# attiny_cool.net
KiCad netlist of a schematic drawn in EAGLE
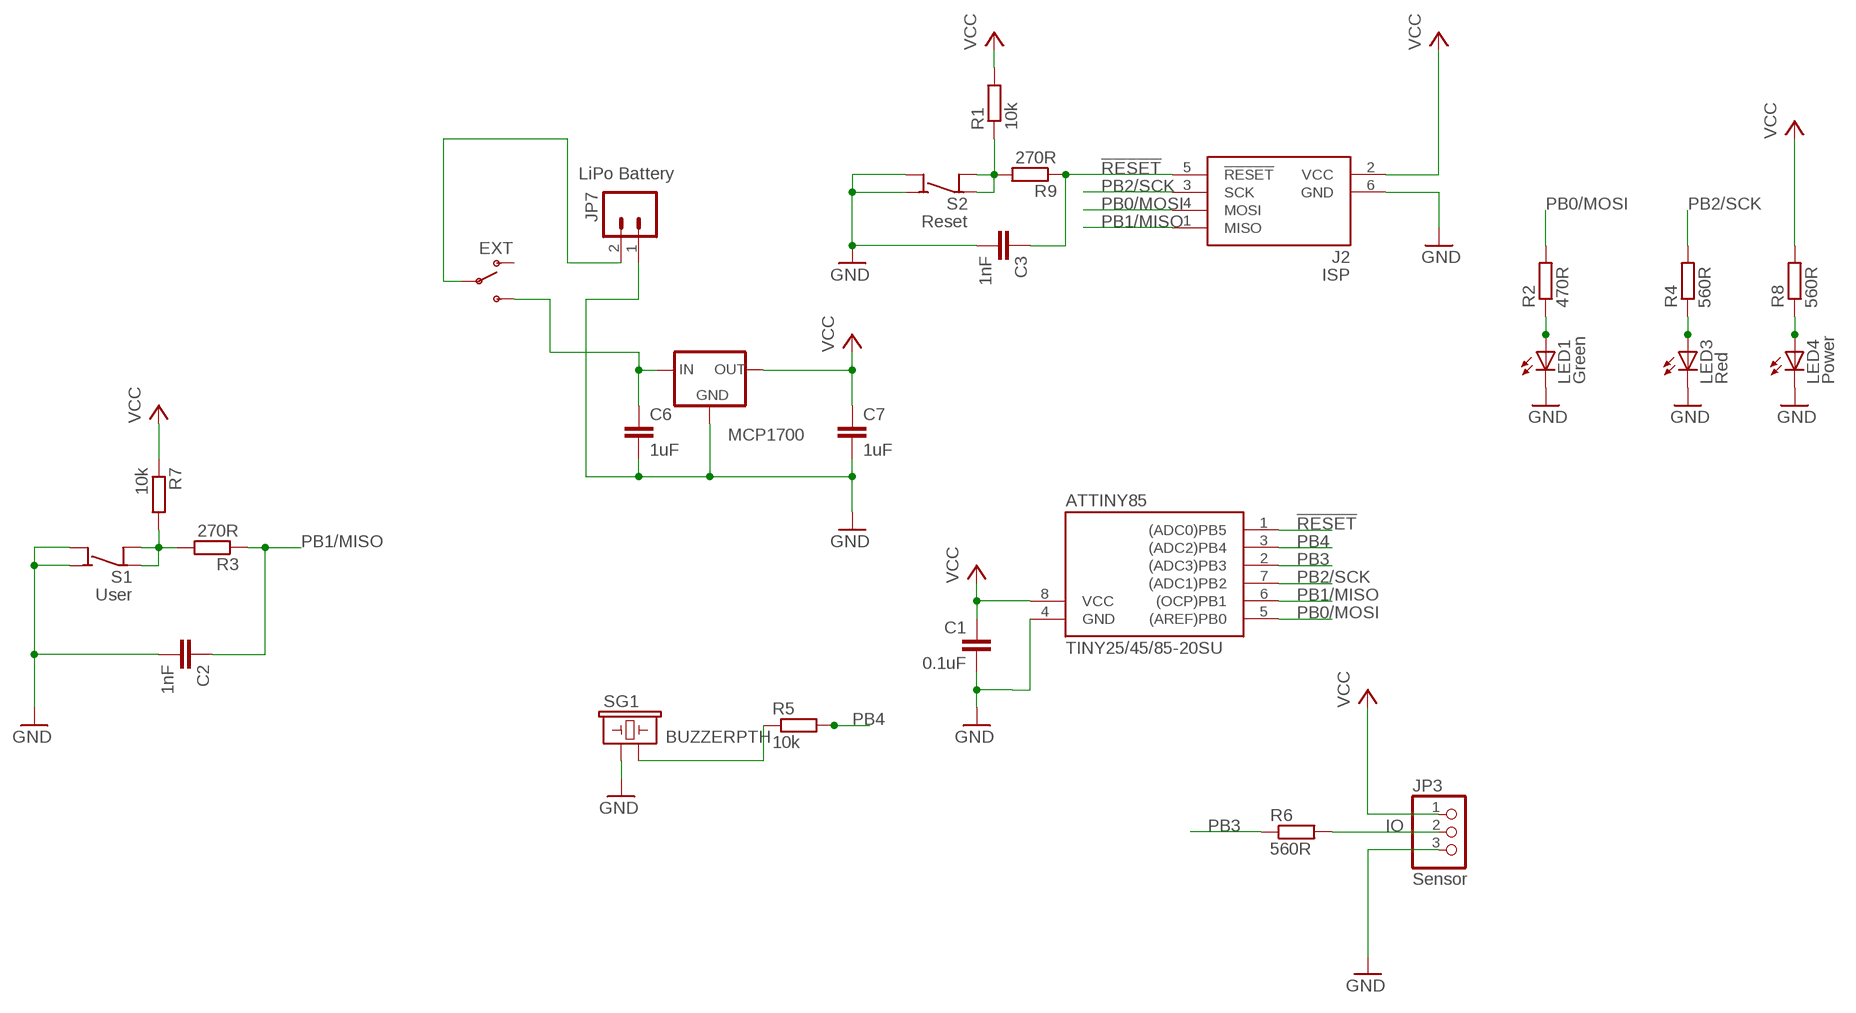
[diagram p0: schematic, sheet 1]

(export (version "E")
  (design (tool "Eeschema 10.0.6"))
  (components
    (comp (ref "ATTINY85")
      (value "TINY25/45/85-20SU")
      (footprint "eagle-import:SOIC8")
      (libsource (lib "eagle-import") (part "TINY25/45/85-20SU"))
    )
    (comp (ref "C1")
      (value "0.1uF")
      (footprint "eagle-import:C0805")
      (libsource (lib "eagle-import") (part "C-EUC0805"))
    )
    (comp (ref "C2")
      (value "1nF")
      (footprint "eagle-import:C0805")
      (libsource (lib "eagle-import") (part "C-EUC0805"))
    )
    (comp (ref "C3")
      (value "1nF")
      (footprint "eagle-import:C0805")
      (libsource (lib "eagle-import") (part "C-EUC0805"))
    )
    (comp (ref "C6")
      (value "1uF")
      (footprint "eagle-import:C0805")
      (libsource (lib "eagle-import") (part "C-EUC0805"))
    )
    (comp (ref "C7")
      (value "1uF")
      (footprint "eagle-import:C0805")
      (libsource (lib "eagle-import") (part "C-EUC0805"))
    )
    (comp (ref "J2")
      (value "ISP")
      (footprint "eagle-import:CON6P2R")
      (libsource (lib "eagle-import") (part "AVRISP6"))
    )
    (comp (ref "JP3")
      (value "Sensor")
      (footprint "eagle-import:1X03")
      (libsource (lib "eagle-import") (part "PINHD-1X3"))
    )
    (comp (ref "JP7")
      (value "LiPo Battery")
      (footprint "eagle-import:JST-2-PTH")
      (libsource (lib "eagle-import") (part "M02JST-PTH-2"))
    )
    (comp (ref "LED1")
      (value "Green")
      (footprint "eagle-import:CHIPLED_1206")
      (libsource (lib "eagle-import") (part "LEDCHIPLED_1206"))
    )
    (comp (ref "LED3")
      (value "Red")
      (footprint "eagle-import:CHIPLED_1206")
      (libsource (lib "eagle-import") (part "LEDCHIPLED_1206"))
    )
    (comp (ref "LED4")
      (value "Power")
      (footprint "eagle-import:CHIPLED_1206")
      (libsource (lib "eagle-import") (part "LEDCHIPLED_1206"))
    )
    (comp (ref "MCP1700")
      (value "MCP1700")
      (footprint "eagle-import:SOT-23")
      (libsource (lib "eagle-import") (part "MCP1700SOT-23"))
    )
    (comp (ref "ON")
      (value "EXT")
      (footprint "eagle-import:SWITCH-SPDT")
      (libsource (lib "eagle-import") (part "SWITCH-SPSTPTH"))
    )
    (comp (ref "R1")
      (value "10k")
      (footprint "eagle-import:R0805")
      (libsource (lib "eagle-import") (part "R-EU_R0805"))
    )
    (comp (ref "R2")
      (value "470R")
      (footprint "eagle-import:R0805")
      (libsource (lib "eagle-import") (part "R-EU_R0805"))
    )
    (comp (ref "R3")
      (value "270R")
      (footprint "eagle-import:R0805")
      (libsource (lib "eagle-import") (part "R-EU_R0805"))
    )
    (comp (ref "R4")
      (value "560R")
      (footprint "eagle-import:R0805")
      (libsource (lib "eagle-import") (part "R-EU_R0805"))
    )
    (comp (ref "R5")
      (value "10k")
      (footprint "eagle-import:R0805")
      (libsource (lib "eagle-import") (part "R-EU_R0805"))
    )
    (comp (ref "R6")
      (value "560R")
      (footprint "eagle-import:R0805")
      (libsource (lib "eagle-import") (part "R-EU_R0805"))
    )
    (comp (ref "R7")
      (value "10k")
      (footprint "eagle-import:R0805")
      (libsource (lib "eagle-import") (part "R-EU_R0805"))
    )
    (comp (ref "R8")
      (value "560R")
      (footprint "eagle-import:R0805")
      (libsource (lib "eagle-import") (part "R-EU_R0805"))
    )
    (comp (ref "R9")
      (value "270R")
      (footprint "eagle-import:R0805")
      (libsource (lib "eagle-import") (part "R-EU_R0805"))
    )
    (comp (ref "S1")
      (value "User")
      (footprint "eagle-import:6MMTACTILE_4PIN")
      (libsource (lib "eagle-import") (part "SPST4"))
    )
    (comp (ref "S2")
      (value "Reset")
      (footprint "eagle-import:6MMTACTILE_4PIN")
      (libsource (lib "eagle-import") (part "SPST4"))
    )
    (comp (ref "SG1")
      (value "BUZZERPTH")
      (footprint "eagle-import:BUZZER-12MM")
      (libsource (lib "eagle-import") (part "BUZZERPTH"))
    )
  )
  (nets
    (net (code "1") (name "/IO") (class "Default")
      (node (ref "JP3") (pin "2") (pinfunction "2_2") (pintype "passive"))
      (node (ref "R6") (pin "2") (pinfunction "2_2") (pintype "passive"))
    )
    (net (code "2") (name "/PB0{slash}MOSI") (class "Default")
      (node (ref "ATTINY85") (pin "5") (pinfunction "(AREF)PB0_5") (pintype "bidirectional"))
      (node (ref "J2") (pin "4") (pinfunction "MOSI_4") (pintype "output"))
      (node (ref "R2") (pin "2") (pinfunction "2_2") (pintype "passive"))
    )
    (net (code "3") (name "/PB1{slash}MISO") (class "Default")
      (node (ref "ATTINY85") (pin "6") (pinfunction "(OCP)PB1_6") (pintype "bidirectional"))
      (node (ref "C2") (pin "1") (pinfunction "1_1") (pintype "passive"))
      (node (ref "J2") (pin "1") (pinfunction "MISO_1") (pintype "input"))
      (node (ref "R3") (pin "1") (pinfunction "1_1") (pintype "passive"))
    )
    (net (code "4") (name "/PB2{slash}SCK") (class "Default")
      (node (ref "ATTINY85") (pin "7") (pinfunction "(ADC1)PB2_7") (pintype "bidirectional"))
      (node (ref "J2") (pin "3") (pinfunction "SCK_3") (pintype "output"))
      (node (ref "R4") (pin "2") (pinfunction "2_2") (pintype "passive"))
    )
    (net (code "5") (name "/PB3") (class "Default")
      (node (ref "ATTINY85") (pin "2") (pinfunction "(ADC3)PB3_2") (pintype "bidirectional"))
      (node (ref "R6") (pin "1") (pinfunction "1_1") (pintype "passive"))
    )
    (net (code "6") (name "/PB4") (class "Default")
      (node (ref "ATTINY85") (pin "3") (pinfunction "(ADC2)PB4_3") (pintype "bidirectional"))
      (node (ref "R5") (pin "2") (pinfunction "2_2") (pintype "passive"))
    )
    (net (code "7") (name "/~{RESET}") (class "Default")
      (node (ref "ATTINY85") (pin "1") (pinfunction "(ADC0)PB5_1") (pintype "bidirectional"))
      (node (ref "C3") (pin "1") (pinfunction "1_1") (pintype "passive"))
      (node (ref "J2") (pin "5") (pinfunction "~{RESET}_5") (pintype "output"))
      (node (ref "R9") (pin "1") (pinfunction "1_1") (pintype "passive"))
    )
    (net (code "8") (name "GND") (class "Default")
      (node (ref "ATTINY85") (pin "4") (pinfunction "GND_4") (pintype "power_in"))
      (node (ref "C1") (pin "2") (pinfunction "2_2") (pintype "passive"))
      (node (ref "C2") (pin "2") (pinfunction "2_2") (pintype "passive"))
      (node (ref "C3") (pin "2") (pinfunction "2_2") (pintype "passive"))
      (node (ref "C6") (pin "2") (pinfunction "2_2") (pintype "passive"))
      (node (ref "C7") (pin "2") (pinfunction "2_2") (pintype "passive"))
      (node (ref "J2") (pin "6") (pinfunction "GND_6") (pintype "power_in"))
      (node (ref "JP3") (pin "3") (pinfunction "3_3") (pintype "passive"))
      (node (ref "JP7") (pin "1") (pinfunction "1_1") (pintype "passive"))
      (node (ref "LED1") (pin "C") (pinfunction "C_C") (pintype "passive"))
      (node (ref "LED3") (pin "C") (pinfunction "C_C") (pintype "passive"))
      (node (ref "LED4") (pin "C") (pinfunction "C_C") (pintype "passive"))
      (node (ref "MCP1700") (pin "1") (pinfunction "GND_1") (pintype "input"))
      (node (ref "S1") (pin "A1") (pinfunction "NO_A1") (pintype "passive"))
      (node (ref "S1") (pin "A2") (pinfunction "NO_A2") (pintype "passive"))
      (node (ref "S2") (pin "A1") (pinfunction "NO_A1") (pintype "passive"))
      (node (ref "S2") (pin "A2") (pinfunction "NO_A2") (pintype "passive"))
      (node (ref "SG1") (pin "+") (pinfunction "1_+") (pintype "passive"))
    )
    (net (code "9") (name "Net-(LED1-PadA)") (class "Default")
      (node (ref "LED1") (pin "A") (pinfunction "A_A") (pintype "passive"))
      (node (ref "R2") (pin "1") (pinfunction "1_1") (pintype "passive"))
    )
    (net (code "10") (name "Net-(LED3-PadA)") (class "Default")
      (node (ref "LED3") (pin "A") (pinfunction "A_A") (pintype "passive"))
      (node (ref "R4") (pin "1") (pinfunction "1_1") (pintype "passive"))
    )
    (net (code "11") (name "Net-(LED4-PadA)") (class "Default")
      (node (ref "LED4") (pin "A") (pinfunction "A_A") (pintype "passive"))
      (node (ref "R8") (pin "1") (pinfunction "1_1") (pintype "passive"))
    )
    (net (code "12") (name "Net-(MCP1700-IN)") (class "Default")
      (node (ref "C6") (pin "1") (pinfunction "1_1") (pintype "passive"))
      (node (ref "MCP1700") (pin "3") (pinfunction "IN_3") (pintype "input"))
      (node (ref "ON") (pin "3") (pinfunction "S_3") (pintype "passive"))
    )
    (net (code "13") (name "Net-(ON-P)") (class "Default")
      (node (ref "JP7") (pin "2") (pinfunction "2_2") (pintype "passive"))
      (node (ref "ON") (pin "2") (pinfunction "P_2") (pintype "passive"))
    )
    (net (code "14") (name "Net-(R1-Pad1)") (class "Default")
      (node (ref "R1") (pin "1") (pinfunction "1_1") (pintype "passive"))
      (node (ref "R9") (pin "2") (pinfunction "2_2") (pintype "passive"))
      (node (ref "S2") (pin "B1") (pinfunction "COM_B1") (pintype "passive"))
      (node (ref "S2") (pin "B2") (pinfunction "COM_B2") (pintype "passive"))
    )
    (net (code "15") (name "Net-(R3-Pad2)") (class "Default")
      (node (ref "R3") (pin "2") (pinfunction "2_2") (pintype "passive"))
      (node (ref "R7") (pin "2") (pinfunction "2_2") (pintype "passive"))
      (node (ref "S1") (pin "B1") (pinfunction "COM_B1") (pintype "passive"))
      (node (ref "S1") (pin "B2") (pinfunction "COM_B2") (pintype "passive"))
    )
    (net (code "16") (name "Net-(SG1-2)") (class "Default")
      (node (ref "R5") (pin "1") (pinfunction "1_1") (pintype "passive"))
      (node (ref "SG1") (pin "-") (pinfunction "2_-") (pintype "passive"))
    )
    (net (code "17") (name "VCC") (class "Default")
      (node (ref "ATTINY85") (pin "8") (pinfunction "VCC_8") (pintype "power_in"))
      (node (ref "C1") (pin "1") (pinfunction "1_1") (pintype "passive"))
      (node (ref "C7") (pin "1") (pinfunction "1_1") (pintype "passive"))
      (node (ref "J2") (pin "2") (pinfunction "VCC_2") (pintype "power_in"))
      (node (ref "JP3") (pin "1") (pinfunction "1_1") (pintype "passive"))
      (node (ref "MCP1700") (pin "2") (pinfunction "OUT_2") (pintype "passive"))
      (node (ref "R1") (pin "2") (pinfunction "2_2") (pintype "passive"))
      (node (ref "R7") (pin "1") (pinfunction "1_1") (pintype "passive"))
      (node (ref "R8") (pin "2") (pinfunction "2_2") (pintype "passive"))
    )
    (net (code "18") (name "unconnected-(ON-O-Pad1)") (class "Default")
      (node (ref "ON") (pin "1") (pinfunction "O_1") (pintype "passive"))
    )
  )
)
